# Dev.net
KiCad netlist of a schematic drawn in Altium Designer
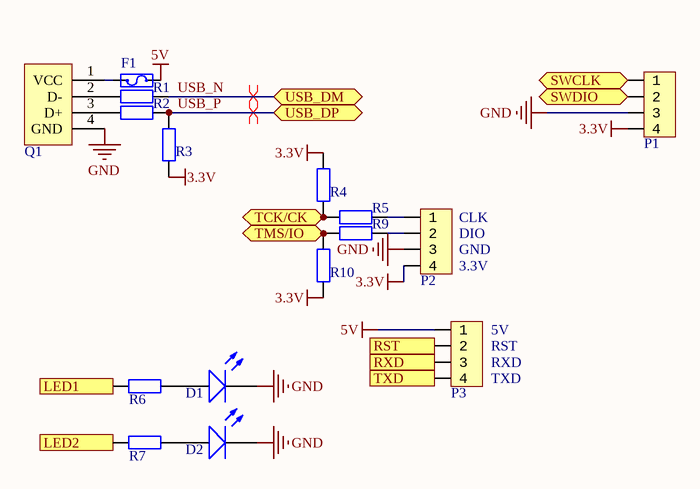
[diagram p0: Dev.SchDoc]

(export (version "E")
  (design (tool "Eeschema 10.0.6"))
  (components
    (comp (ref "D1")
      (value "RED")
      (footprint "LED-0603")
      (description "发光二极管")
      (libsource (lib "Power_Lib_Altium") (part "LED"))
    )
    (comp (ref "D2")
      (value "GREEN")
      (footprint "LED-0603")
      (description "发光二极管")
      (libsource (lib "Power_Lib_Altium") (part "LED"))
    )
    (comp (ref "F1")
      (value "Fuse")
      (footprint "Fuse_0805")
      (description "6V 500mA 保险丝")
      (libsource (lib "Power_Lib_Altium") (part "Fuse"))
    )
    (comp (ref "P1")
      (value "HDR1x4_2.54")
      (footprint "HDR1x4_2.54_180")
      (description "Header")
      (libsource (lib "Power_Lib_Altium") (part "HDR1x4_2.54"))
    )
    (comp (ref "P2")
      (value "HDR1x4_2.54")
      (footprint "HDR1X4_2.54_180H")
      (description "Header")
      (libsource (lib "Power_Lib_Altium") (part "HDR1x4_2.54"))
    )
    (comp (ref "P3")
      (value "HDR1x4_2.54")
      (footprint "HDR1X4_2.54_180H")
      (description "Header")
      (libsource (lib "Power_Lib_Altium") (part "HDR1x4_2.54"))
    )
    (comp (ref "Q1")
      (value "USB A")
      (footprint "USB_A(M)_DIP")
      (description "USB 接口")
      (libsource (lib "Power_Lib_Altium") (part "USB A"))
    )
    (comp (ref "R1")
      (value "22R")
      (footprint "R-0603")
      (description "贴片电阻")
      (libsource (lib "") (part "RES_1"))
    )
    (comp (ref "R2")
      (value "22R")
      (footprint "R-0603")
      (description "贴片电阻")
      (libsource (lib "") (part "RES_1"))
    )
    (comp (ref "R3")
      (value "1.5K")
      (footprint "R-0603")
      (description "贴片电阻")
      (libsource (lib "") (part "RES_2"))
    )
    (comp (ref "R4")
      (value "1R")
      (footprint "R-0603")
      (description "贴片电阻")
      (libsource (lib "") (part "RES_2"))
    )
    (comp (ref "R5")
      (value "22R")
      (footprint "R-0603")
      (description "贴片电阻")
      (libsource (lib "") (part "RES_1"))
    )
    (comp (ref "R6")
      (value "10K")
      (footprint "R-0603")
      (description "贴片电阻")
      (libsource (lib "Power_Lib_Altium") (part "RES"))
    )
    (comp (ref "R7")
      (value "10K")
      (footprint "R-0603")
      (description "贴片电阻")
      (libsource (lib "Power_Lib_Altium") (part "RES"))
    )
    (comp (ref "R9")
      (value "22R")
      (footprint "R-0603")
      (description "贴片电阻")
      (libsource (lib "") (part "RES_1"))
    )
    (comp (ref "R10")
      (value "1R")
      (footprint "R-0603")
      (description "贴片电阻")
      (libsource (lib "") (part "RES_2"))
    )
  )
  (nets
    (net (code "1") (name "/LED1") (class "Default")
      (node (ref "R6") (pin "2") (pinfunction "2_2") (pintype "passive"))
    )
    (net (code "2") (name "/LED2") (class "Default")
      (node (ref "R7") (pin "2") (pinfunction "2_2") (pintype "passive"))
    )
    (net (code "3") (name "/RST") (class "Default")
      (node (ref "P3") (pin "2") (pinfunction "2_2") (pintype "passive"))
    )
    (net (code "4") (name "/RXD") (class "Default")
      (node (ref "P3") (pin "3") (pinfunction "3_3") (pintype "passive"))
    )
    (net (code "5") (name "/SWCLK") (class "Default")
      (node (ref "P1") (pin "1") (pinfunction "1_1") (pintype "passive"))
    )
    (net (code "6") (name "/SWDIO") (class "Default")
      (node (ref "P1") (pin "2") (pinfunction "2_2") (pintype "passive"))
    )
    (net (code "7") (name "/TCK{slash}CK") (class "Default")
      (node (ref "R4") (pin "1") (pinfunction "1_1") (pintype "passive"))
      (node (ref "R5") (pin "1") (pinfunction "1_1") (pintype "passive"))
    )
    (net (code "8") (name "/TMS{slash}IO") (class "Default")
      (node (ref "R10") (pin "2") (pinfunction "2_2") (pintype "passive"))
      (node (ref "R9") (pin "1") (pinfunction "1_1") (pintype "passive"))
    )
    (net (code "9") (name "/TXD") (class "Default")
      (node (ref "P3") (pin "4") (pinfunction "4_4") (pintype "passive"))
    )
    (net (code "10") (name "/USB_N") (class "Default")
      (node (ref "R1") (pin "2") (pinfunction "2_2") (pintype "passive"))
    )
    (net (code "11") (name "/USB_P") (class "Default")
      (node (ref "R2") (pin "2") (pinfunction "2_2") (pintype "passive"))
      (node (ref "R3") (pin "2") (pinfunction "2_2") (pintype "passive"))
    )
    (net (code "12") (name "3.3V") (class "Default")
      (node (ref "P1") (pin "4") (pinfunction "4_4") (pintype "passive"))
      (node (ref "P2") (pin "4") (pinfunction "4_4") (pintype "passive"))
      (node (ref "R10") (pin "1") (pinfunction "1_1") (pintype "passive"))
      (node (ref "R3") (pin "1") (pinfunction "1_1") (pintype "passive"))
      (node (ref "R4") (pin "2") (pinfunction "2_2") (pintype "passive"))
    )
    (net (code "13") (name "5V") (class "Default")
      (node (ref "F1") (pin "2") (pinfunction "2_2") (pintype "passive"))
      (node (ref "P3") (pin "1") (pinfunction "1_1") (pintype "passive"))
    )
    (net (code "14") (name "GND") (class "Default")
      (node (ref "D1") (pin "K") (pinfunction "K_K") (pintype "passive"))
      (node (ref "D2") (pin "K") (pinfunction "K_K") (pintype "passive"))
      (node (ref "P1") (pin "3") (pinfunction "3_3") (pintype "passive"))
      (node (ref "P2") (pin "3") (pinfunction "3_3") (pintype "passive"))
      (node (ref "Q1") (pin "4") (pinfunction "GND_4") (pintype "passive"))
    )
    (net (code "15") (name "Net-(D1-PadA)") (class "Default")
      (node (ref "D1") (pin "A") (pinfunction "A_A") (pintype "passive"))
      (node (ref "R6") (pin "1") (pinfunction "1_1") (pintype "passive"))
    )
    (net (code "16") (name "Net-(D2-PadA)") (class "Default")
      (node (ref "D2") (pin "A") (pinfunction "A_A") (pintype "passive"))
      (node (ref "R7") (pin "1") (pinfunction "1_1") (pintype "passive"))
    )
    (net (code "17") (name "Net-(P2-Pad1)") (class "Default")
      (node (ref "P2") (pin "1") (pinfunction "1_1") (pintype "passive"))
      (node (ref "R5") (pin "2") (pinfunction "2_2") (pintype "passive"))
    )
    (net (code "18") (name "Net-(P2-Pad2)") (class "Default")
      (node (ref "P2") (pin "2") (pinfunction "2_2") (pintype "passive"))
      (node (ref "R9") (pin "2") (pinfunction "2_2") (pintype "passive"))
    )
    (net (code "19") (name "Net-(Q1-D+)") (class "Default")
      (node (ref "Q1") (pin "3") (pinfunction "D+_3") (pintype "passive"))
      (node (ref "R2") (pin "1") (pinfunction "1_1") (pintype "passive"))
    )
    (net (code "20") (name "Net-(Q1-D-)") (class "Default")
      (node (ref "Q1") (pin "2") (pinfunction "D-_2") (pintype "passive"))
      (node (ref "R1") (pin "1") (pinfunction "1_1") (pintype "passive"))
    )
    (net (code "21") (name "Net-(Q1-VCC)") (class "Default")
      (node (ref "F1") (pin "1") (pinfunction "1_1") (pintype "passive"))
      (node (ref "Q1") (pin "1") (pinfunction "VCC_1") (pintype "passive"))
    )
  )
)
